# Teensy_MouseV2_0_bottom_Deck.net
KiCad netlist of a schematic drawn in EAGLE
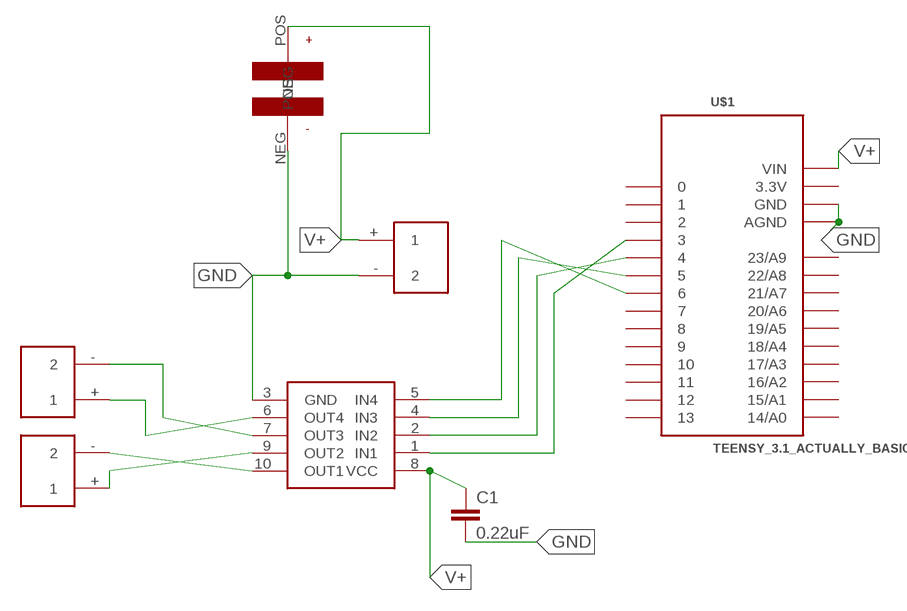
[diagram p0: schematic, sheet 1]

(export (version "E")
  (design (tool "Eeschema 10.0.6"))
  (components
    (comp (ref "C1")
      (value "0.22uF")
      (footprint "eagle-import:0603-CAP")
      (libsource (lib "eagle-import") (part "0.22UF50V-20%,+80%(0603)"))
    )
    (comp (ref "U$1")
      (value "TEENSY_3.1_ACTUALLY_BASIC")
      (footprint "eagle-import:TEENSY_3.0_ACTUALLY_BASIC")
      (libsource (lib "eagle-import") (part "TEENSY_3.1_ACTUALLY_BASIC"))
    )
    (comp (ref "U$2")
      (value "TEENSYMOUSEMOTORS")
      (footprint "eagle-import:TEENSYMOUSEMOTRS")
      (libsource (lib "eagle-import") (part "TEENSYMOUSEMOTORS"))
    )
    (comp (ref "U$3")
      (value "TEENSYMOUSEMOTORS")
      (footprint "eagle-import:TEENSYMOUSEMOTRS")
      (libsource (lib "eagle-import") (part "TEENSYMOUSEMOTORS"))
    )
    (comp (ref "U$4")
      (value "PICOBLADE2X")
      (footprint "eagle-import:PICOBLADE2X")
      (libsource (lib "eagle-import") (part "PICOBLADE2X"))
    )
    (comp (ref "U$5")
      (value "47UFBUTTONCAP")
      (footprint "eagle-import:ALUMINIUMELECTOCAP")
      (libsource (lib "eagle-import") (part "47UFBUTTONCAP"))
    )
    (comp (ref "U$7")
      (value "A3901DUALHBRIDGE")
      (footprint "eagle-import:10WFDFN")
      (libsource (lib "eagle-import") (part "A3901DUALHBRIDGE"))
    )
  )
  (nets
    (net (code "1") (name "/3.3V") (class "Default")
      (node (ref "U$1") (pin "3.3V") (pinfunction "3.3V_3.3V") (pintype "power_in"))
    )
    (net (code "2") (name "GND") (class "Default")
      (node (ref "C1") (pin "2") (pinfunction "2_2") (pintype "passive"))
      (node (ref "U$1") (pin "AGND") (pinfunction "AGND_AGND") (pintype "power_in"))
      (node (ref "U$1") (pin "GND") (pinfunction "GND_GND") (pintype "power_in"))
      (node (ref "U$4") (pin "-") (pinfunction "2_-") (pintype "bidirectional"))
      (node (ref "U$5") (pin "NEG") (pinfunction "NEG_NEG") (pintype "bidirectional"))
      (node (ref "U$7") (pin "3") (pinfunction "GND_3") (pintype "bidirectional"))
    )
    (net (code "3") (name "Net-(U$2-1)") (class "Default")
      (node (ref "U$2") (pin "+") (pinfunction "1_+") (pintype "bidirectional"))
      (node (ref "U$7") (pin "9") (pinfunction "OUT2_9") (pintype "bidirectional"))
    )
    (net (code "4") (name "Net-(U$2-2)") (class "Default")
      (node (ref "U$2") (pin "-") (pinfunction "2_-") (pintype "bidirectional"))
      (node (ref "U$7") (pin "10") (pinfunction "OUT1_10") (pintype "bidirectional"))
    )
    (net (code "5") (name "Net-(U$3-1)") (class "Default")
      (node (ref "U$3") (pin "+") (pinfunction "1_+") (pintype "bidirectional"))
      (node (ref "U$7") (pin "6") (pinfunction "OUT4_6") (pintype "bidirectional"))
    )
    (net (code "6") (name "Net-(U$3-2)") (class "Default")
      (node (ref "U$3") (pin "-") (pinfunction "2_-") (pintype "bidirectional"))
      (node (ref "U$7") (pin "7") (pinfunction "OUT3_7") (pintype "bidirectional"))
    )
    (net (code "7") (name "Net-(U$7-IN1)") (class "Default")
      (node (ref "U$1") (pin "3") (pinfunction "3_3") (pintype "bidirectional"))
      (node (ref "U$7") (pin "1") (pinfunction "IN1_1") (pintype "bidirectional"))
    )
    (net (code "8") (name "Net-(U$7-IN2)") (class "Default")
      (node (ref "U$1") (pin "4") (pinfunction "4_4") (pintype "bidirectional"))
      (node (ref "U$7") (pin "2") (pinfunction "IN2_2") (pintype "bidirectional"))
    )
    (net (code "9") (name "Net-(U$7-IN3)") (class "Default")
      (node (ref "U$1") (pin "5") (pinfunction "5_5") (pintype "bidirectional"))
      (node (ref "U$7") (pin "4") (pinfunction "IN3_4") (pintype "bidirectional"))
    )
    (net (code "10") (name "Net-(U$7-IN4)") (class "Default")
      (node (ref "U$1") (pin "6") (pinfunction "6_6") (pintype "bidirectional"))
      (node (ref "U$7") (pin "5") (pinfunction "IN4_5") (pintype "bidirectional"))
    )
    (net (code "11") (name "V+") (class "Default")
      (node (ref "C1") (pin "1") (pinfunction "1_1") (pintype "passive"))
      (node (ref "U$1") (pin "VIN") (pinfunction "VIN_VIN") (pintype "power_in"))
      (node (ref "U$4") (pin "+") (pinfunction "1_+") (pintype "bidirectional"))
      (node (ref "U$5") (pin "POS") (pinfunction "POS_POS") (pintype "bidirectional"))
      (node (ref "U$7") (pin "8") (pinfunction "VCC_8") (pintype "bidirectional"))
    )
    (net (code "12") (name "unconnected-(U$1-Pad0)") (class "Default")
      (node (ref "U$1") (pin "0") (pinfunction "0_0") (pintype "bidirectional"))
    )
    (net (code "13") (name "unconnected-(U$1-Pad1)") (class "Default")
      (node (ref "U$1") (pin "1") (pinfunction "1_1") (pintype "bidirectional"))
    )
    (net (code "14") (name "unconnected-(U$1-Pad2)") (class "Default")
      (node (ref "U$1") (pin "2") (pinfunction "2_2") (pintype "bidirectional"))
    )
    (net (code "15") (name "unconnected-(U$1-Pad7)") (class "Default")
      (node (ref "U$1") (pin "7") (pinfunction "7_7") (pintype "bidirectional"))
    )
    (net (code "16") (name "unconnected-(U$1-Pad8)") (class "Default")
      (node (ref "U$1") (pin "8") (pinfunction "8_8") (pintype "bidirectional"))
    )
    (net (code "17") (name "unconnected-(U$1-Pad9)") (class "Default")
      (node (ref "U$1") (pin "9") (pinfunction "9_9") (pintype "bidirectional"))
    )
    (net (code "18") (name "unconnected-(U$1-Pad10)") (class "Default")
      (node (ref "U$1") (pin "10") (pinfunction "10_10") (pintype "bidirectional"))
    )
    (net (code "19") (name "unconnected-(U$1-Pad11)") (class "Default")
      (node (ref "U$1") (pin "11") (pinfunction "11_11") (pintype "bidirectional"))
    )
    (net (code "20") (name "unconnected-(U$1-Pad12)") (class "Default")
      (node (ref "U$1") (pin "12") (pinfunction "12_12") (pintype "bidirectional"))
    )
    (net (code "21") (name "unconnected-(U$1-Pad13)") (class "Default")
      (node (ref "U$1") (pin "13") (pinfunction "13_13") (pintype "bidirectional"))
    )
    (net (code "22") (name "unconnected-(U$1-Pad14{slash}A0)") (class "Default")
      (node (ref "U$1") (pin "14/A0") (pinfunction "14/A0_14/A0") (pintype "bidirectional"))
    )
    (net (code "23") (name "unconnected-(U$1-Pad15{slash}A1)") (class "Default")
      (node (ref "U$1") (pin "15/A1") (pinfunction "15/A1_15/A1") (pintype "bidirectional"))
    )
    (net (code "24") (name "unconnected-(U$1-Pad16{slash}A2)") (class "Default")
      (node (ref "U$1") (pin "16/A2") (pinfunction "16/A2_16/A2") (pintype "bidirectional"))
    )
    (net (code "25") (name "unconnected-(U$1-Pad17{slash}A3)") (class "Default")
      (node (ref "U$1") (pin "17/A3") (pinfunction "17/A3_17/A3") (pintype "bidirectional"))
    )
    (net (code "26") (name "unconnected-(U$1-Pad18{slash}A4)") (class "Default")
      (node (ref "U$1") (pin "18/A4") (pinfunction "18/A4_18/A4") (pintype "bidirectional"))
    )
    (net (code "27") (name "unconnected-(U$1-Pad19{slash}A5)") (class "Default")
      (node (ref "U$1") (pin "19/A5") (pinfunction "19/A5_19/A5") (pintype "bidirectional"))
    )
    (net (code "28") (name "unconnected-(U$1-Pad20{slash}A6)") (class "Default")
      (node (ref "U$1") (pin "20/A6") (pinfunction "20/A6_20/A6") (pintype "bidirectional"))
    )
    (net (code "29") (name "unconnected-(U$1-Pad21{slash}A7)") (class "Default")
      (node (ref "U$1") (pin "21/A7") (pinfunction "21/A7_21/A7") (pintype "bidirectional"))
    )
    (net (code "30") (name "unconnected-(U$1-Pad22{slash}A8)") (class "Default")
      (node (ref "U$1") (pin "22/A8") (pinfunction "22/A8_22/A8") (pintype "bidirectional"))
    )
    (net (code "31") (name "unconnected-(U$1-Pad23{slash}A9)") (class "Default")
      (node (ref "U$1") (pin "23/A9") (pinfunction "23/A9_23/A9") (pintype "bidirectional"))
    )
  )
)
